# PSU.net
KiCad netlist of a schematic drawn in Altium Designer
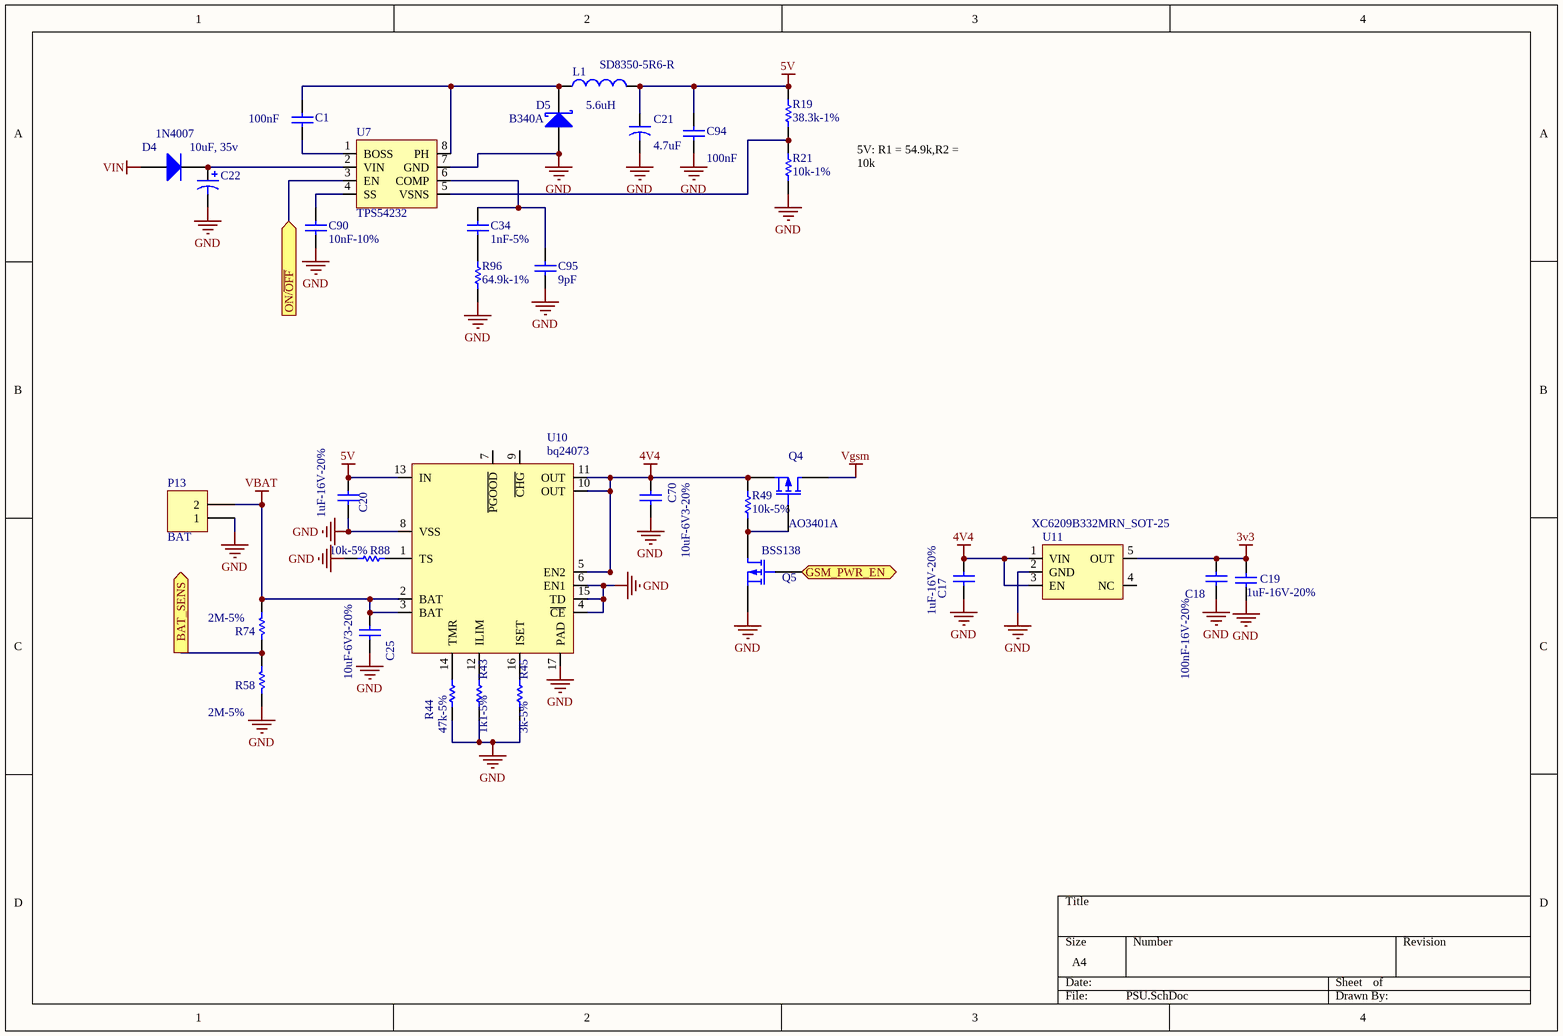
[diagram p0: PSU.SchDoc]

(export (version "E")
  (design (tool "Eeschema 10.0.6"))
  (components
    (comp (ref "C1")
      (value "100nF")
      (footprint "0402_TYPE1")
      (description "Capacitor")
      (fields (field (name "PUBLISHER") "Altium Limited"))
      (libsource (lib "Miscellaneous Devices") (part "Cap"))
    )
    (comp (ref "C17")
      (value "1uF-16V-20%")
      (footprint "C0603")
      (description "CAP CER 1UF 16V Y5V 0603")
      (fields
        (field (name "MANUFACTURER") "Yageo")
        (field (name "DIGI-KEY PART NUMBER") "311-1372-1-ND")
        (field (name "PUBLISHER") "Altium Limited")
      )
      (libsource (lib "Miscellaneous Devices") (part "Cap"))
    )
    (comp (ref "C18")
      (value "100nF-16V-20%")
      (footprint "0402_TYPE1")
      (description "CAP CER 0.1UF 16V Y5V 0402")
      (fields
        (field (name "MANUFACTURER") "Yageo")
        (field (name "DIGI-KEY PART NUMBER") "311-1047-1-ND")
        (field (name "PUBLISHER") "Altium Limited")
      )
      (libsource (lib "Miscellaneous Devices") (part "Cap"))
    )
    (comp (ref "C19")
      (value "1uF-16V-20%")
      (footprint "C0603")
      (description "CAP CER 1UF 16V Y5V 0603")
      (fields
        (field (name "MANUFACTURER") "Yageo")
        (field (name "DIGI-KEY PART NUMBER") "311-1372-1-ND")
        (field (name "PUBLISHER") "Altium Limited")
      )
      (libsource (lib "Miscellaneous Devices") (part "Cap"))
    )
    (comp (ref "C20")
      (value "1uF-16V-20%")
      (footprint "C0603")
      (description "CAP CER 1UF 16V Y5V 0603")
      (fields
        (field (name "MANUFACTURER") "Yageo")
        (field (name "DIGI-KEY PART NUMBER") "311-1372-1-ND")
        (field (name "PUBLISHER") "Altium Limited")
      )
      (libsource (lib "Miscellaneous Devices") (part "Cap"))
    )
    (comp (ref "C21")
      (value "4.7uF")
      (footprint "C1206")
      (description "Capacitor")
      (fields (field (name "PUBLISHER") "Altium Limited"))
      (libsource (lib "Miscellaneous Devices") (part "Cap2"))
    )
    (comp (ref "C22")
      (value "10uF, 35v")
      (footprint "CAPACITOR SIZE_C(D5.3)")
      (description "CAP ALUM 10UF 35V 20% SMD")
      (fields
        (field (name "DIGI-KEY PART NUMBER") "PCE3947TR-ND")
        (field (name "MANUFACTURER") "Panasonic Electronic Components")
        (field (name "PUBLISHER") "Altium Limited")
      )
      (libsource (lib "Miscellaneous Devices") (part "Cap Pol3"))
    )
    (comp (ref "C25")
      (value "10uF-6V3-20%")
      (footprint "C0603")
      (description "CAP CER 10UF 6.3V 20% X5R 0603")
      (fields
        (field (name "MANUFACTURER") "Yageo")
        (field (name "DIGI-KEY PART NUMBER") "311-1448-1-ND")
        (field (name "PUBLISHER") "Altium Limited")
      )
      (libsource (lib "Miscellaneous Devices") (part "Cap"))
    )
    (comp (ref "C34")
      (value "1nF-5%")
      (footprint "0402_TYPE1")
      (description "Non-Polarized Capacitor")
      (fields (field (name "DIGI-KEY PART NUMBER") "311-1122-1-ND") (field (name "MANUFACTURER") "Yageo"))
      (libsource (lib "Capacitor") (part "1nF-50V-C0805"))
    )
    (comp (ref "C70")
      (value "10uF-6V3-20%")
      (footprint "C0603")
      (description "CAP CER 10UF 6.3V 20% X5R 0603")
      (fields
        (field (name "MANUFACTURER") "Yageo")
        (field (name "DIGI-KEY PART NUMBER") "311-1448-1-ND")
        (field (name "PUBLISHER") "Altium Limited")
      )
      (libsource (lib "Miscellaneous Devices") (part "Cap"))
    )
    (comp (ref "C90")
      (value "10nF-10%")
      (footprint "0402_TYPE1")
      (description "Non-Polarized Capacitor")
      (fields (field (name "DIGI-KEY PART NUMBER") "311-1136-1-ND") (field (name "MANUFACTURER") "Yageo"))
      (libsource (lib "Capacitor") (part "10nF-50V-C0805"))
    )
    (comp (ref "C94")
      (value "100nF")
      (footprint "0402_TYPE1")
      (description "Capacitor")
      (fields (field (name "PUBLISHER") "Altium Limited"))
      (libsource (lib "Miscellaneous Devices") (part "Cap"))
    )
    (comp (ref "C95")
      (value "9pF")
      (footprint "0402_TYPE1")
      (description "Non-Polarized Capacitor")
      (fields (field (name "DIGI-KEY PART NUMBER") "311-1098-1-ND") (field (name "MANUFACTURER") "Yageo"))
      (libsource (lib "Capacitor") (part "9pF-50V-C0805"))
    )
    (comp (ref "D4")
      (value "1N4007")
      (footprint "DO-214AC (SMA)")
      (description "DIODE GEN PURPOSE 1000V 1A SMA")
      (fields
        (field (name "DIGI-KEY PART NUMBER") "641-1018-1-ND")
        (field (name "MANUFACTURER PART NUMBER") "CGRA4007-G")
        (field (name "PUBLISHER") "Altium Limited")
      )
      (libsource (lib "Miscellaneous Devices") (part "Diode"))
    )
    (comp (ref "D5")
      (value "B340A")
      (footprint "DO-214AC (SMA)")
      (description "DIODE SCHOTTKY 40V 3A SMA")
      (fields
        (field (name "DIGI-KEY PART NUMBER") "B340A-E3/61TGITR-ND")
        (field (name "MANUFACTURER PART NUMBER") "B340A-E3/61T")
        (field (name "PUBLISHER") "Altium Limited")
      )
      (libsource (lib "Miscellaneous Devices") (part "D Schottky"))
    )
    (comp (ref "L1")
      (value "SD8350-5R6-R")
      (footprint "SD8350-5R6-R")
      (description "Digikey part SD8350-4R7-R")
      (fields (field (name "ALTIUM_VALUE") "5.6uH") (field (name "PUBLISHER") "Altium Limited"))
      (libsource (lib "Miscellaneous Devices") (part "Inductor"))
    )
    (comp (ref "P13")
      (value "BAT")
      (footprint "HDR1X2")
      (description "Header, 2-Pin")
      (fields (field (name "PUBLISHER") "Altium Limited"))
      (libsource (lib "Miscellaneous Connectors") (part "Header 2"))
    )
    (comp (ref "Q4")
      (value "AO3401A")
      (footprint "SOT23-3")
      (description "MOSFET P-CH -30V -4.3A SOT23")
      (fields
        (field (name "DIGI-KEY PART NUMBER") "785-1001-1-ND")
        (field (name "MANUFACTURER") "Alpha & Omega Semiconductor Inc")
        (field (name "PUBLISHER") "Altium Limited")
      )
      (libsource (lib "Miscellaneous Devices") (part "MOSFET-P"))
    )
    (comp (ref "Q5")
      (value "BSS138")
      (footprint "SOT23-3")
      (description "MOSFET N-CH 50V 200MA SOT23-3")
      (fields
        (field (name "DIGI-KEY PART NUMBER") "BSS138-FDICT-ND")
        (field (name "MANUFACTURER") "Diodes Inc")
        (field (name "PUBLISHER") "Altium Limited")
      )
      (libsource (lib "") (part "MOSFET-P_1"))
    )
    (comp (ref "R19")
      (value "38.3k-1%")
      (footprint "R0402_TYPE1")
      (description "RES 38.3k OHM 1/4W 1% 0805 SMD")
      (fields (field (name "DIGI-KEY PART NUMBER") "311-38.3KCRTR-ND") (field (name "MANUFACTURER") "Yageo"))
      (libsource (lib "All_Resistor") (part "38.3k-1%-R0805"))
    )
    (comp (ref "R21")
      (value "10k-1%")
      (footprint "R0402_TYPE1")
      (description "RES 10k OHM 1/4W 1% 0805 SMD")
      (fields (field (name "DIGI-KEY PART NUMBER") "311-10.0KCRTR-ND") (field (name "MANUFACTURER") "Yageo"))
      (libsource (lib "All_Resistor") (part "10k-1%-R0805"))
    )
    (comp (ref "R43")
      (value "1k1-5%")
      (footprint "R0402_TYPE1")
      (description "RES 1.1K OHM 1/16W 5% 0402 SMD")
      (fields
        (field (name "DIGI-KEY PART NUMBER") "311-1.1KJRCT-ND")
        (field (name "MANUFACTURER") "Yageo")
        (field (name "PUBLISHER") "Altium Limited")
      )
      (libsource (lib "Miscellaneous Devices") (part "Res1"))
    )
    (comp (ref "R44")
      (value "47k-5%")
      (footprint "R0402_TYPE1")
      (description "RES 47K OHM 1/16W 5% 0402 SMD")
      (fields
        (field (name "DIGI-KEY PART NUMBER") "311-47KJRCT-ND")
        (field (name "MANUFACTURER") "Yageo")
        (field (name "PUBLISHER") "Altium Limited")
      )
      (libsource (lib "Miscellaneous Devices") (part "Res1"))
    )
    (comp (ref "R45")
      (value "3k-5%")
      (footprint "R0402_TYPE1")
      (description "RES 1.5K OHM 1/16W 5% 0402 SMD")
      (fields
        (field (name "DIGI-KEY PART NUMBER") "311-3.0KJRCT-ND")
        (field (name "MANUFACTURER") "Yageo")
        (field (name "PUBLISHER") "Altium Limited")
      )
      (libsource (lib "Miscellaneous Devices") (part "Res1"))
    )
    (comp (ref "R49")
      (value "10k-5%")
      (footprint "R0402_TYPE1")
      (description "RES 10K OHM 1/16W 5% 0402 SMD")
      (fields
        (field (name "DIGI-KEY PART NUMBER") "311-10KJRCT-ND")
        (field (name "MANUFACTURER") "Yageo")
        (field (name "PUBLISHER") "Altium Limited")
      )
      (libsource (lib "Miscellaneous Devices") (part "Res1"))
    )
    (comp (ref "R58")
      (value "2M-5%")
      (footprint "R0402_TYPE1")
      (description "RES 100K OHM 1/16W 5% 0402 SMD")
      (fields
        (field (name "DIGI-KEY PART NUMBER") "1276-4293-2-ND")
        (field (name "MANUFACTURER") "Samsung Electro-Mechanics America, Inc")
        (field (name "PUBLISHER") "Altium Limited")
      )
      (libsource (lib "Miscellaneous Devices") (part "Res1"))
    )
    (comp (ref "R74")
      (value "2M-5%")
      (footprint "R0402_TYPE1")
      (description "RES 2M OHM 1/16W 1% 0402")
      (fields
        (field (name "DIGI-KEY PART NUMBER") "1276-4293-2-ND")
        (field (name "MANUFACTURER") "Samsung Electro-Mechanics America, Inc")
        (field (name "PUBLISHER") "Altium Limited")
      )
      (libsource (lib "Miscellaneous Devices") (part "Res1"))
    )
    (comp (ref "R88")
      (value "10k-5%")
      (footprint "R0402_TYPE1")
      (description "RES 10K OHM 1/16W 5% 0402 SMD")
      (fields
        (field (name "DIGI-KEY PART NUMBER") "311-10KJRCT-ND")
        (field (name "MANUFACTURER") "Yageo")
        (field (name "PUBLISHER") "Altium Limited")
      )
      (libsource (lib "Miscellaneous Devices") (part "Res1"))
    )
    (comp (ref "R96")
      (value "64.9k-1%")
      (footprint "R0402_TYPE1")
      (description "RES 64.9k OHM 1/4W 1% 0805 SMD")
      (fields (field (name "DIGI-KEY PART NUMBER") "311-64.9KCRTR-ND") (field (name "MANUFACTURER") "Yageo"))
      (libsource (lib "All_Resistor") (part "64.9k-1%-R0805"))
    )
    (comp (ref "U7")
      (value "TPS54232")
      (footprint "SOIC127P600-8AL")
      (libsource (lib "TPS54232") (part "Component_1"))
    )
    (comp (ref "U10")
      (value "bq24073")
      (footprint "pq24073")
      (description "IC LI-ION CHARGE/PWR MGMT 16-QFN")
      (fields
        (field (name "DIGI-KEY PART NUMBER") "296-23839-1-ND")
        (field (name "MANUFACTURER") "Texas Instruments")
      )
      (libsource (lib "TI_Power") (part "BATTERY_CHARGER"))
    )
    (comp (ref "U11")
      (value "XC6209B332MRN_SOT-25")
      (footprint "SOT23-5")
      (fields (field (name "MANUFACTURER") "Tyrone"))
      (libsource (lib "Schlib1") (part "XC6209B332MRN_SOT-25"))
    )
  )
  (nets
    (net (code "1") (name "/BAT_SENS") (class "Default")
      (node (ref "R58") (pin "2") (pinfunction "2_2") (pintype "passive"))
      (node (ref "R74") (pin "1") (pinfunction "1_1") (pintype "passive"))
    )
    (net (code "2") (name "/GSM_PWR_EN") (class "Default")
      (node (ref "Q5") (pin "1") (pinfunction "G_1") (pintype "passive"))
    )
    (net (code "3") (name "/ON{slash}~{OFF}") (class "Default")
      (node (ref "U7") (pin "3") (pinfunction "EN_3") (pintype "passive"))
    )
    (net (code "4") (name "3v3") (class "Default")
      (node (ref "C18") (pin "2") (pinfunction "2_2") (pintype "passive"))
      (node (ref "C19") (pin "1") (pinfunction "1_1") (pintype "passive"))
      (node (ref "U11") (pin "5") (pinfunction "OUT_5") (pintype "passive"))
    )
    (net (code "5") (name "4V4") (class "Default")
      (node (ref "C17") (pin "1") (pinfunction "1_1") (pintype "passive"))
      (node (ref "C70") (pin "2") (pinfunction "2_2") (pintype "passive"))
      (node (ref "Q4") (pin "2") (pinfunction "S_2") (pintype "passive"))
      (node (ref "R49") (pin "1") (pinfunction "1_1") (pintype "passive"))
      (node (ref "U10") (pin "10") (pinfunction "OUT_10") (pintype "passive"))
      (node (ref "U10") (pin "11") (pinfunction "OUT_11") (pintype "passive"))
      (node (ref "U10") (pin "5") (pinfunction "EN2_5") (pintype "passive"))
      (node (ref "U11") (pin "1") (pinfunction "VIN_1") (pintype "passive"))
      (node (ref "U11") (pin "3") (pinfunction "EN_3") (pintype "passive"))
    )
    (net (code "6") (name "5V") (class "Default")
      (node (ref "C20") (pin "2") (pinfunction "2_2") (pintype "passive"))
      (node (ref "C21") (pin "1") (pinfunction "1_1") (pintype "passive"))
      (node (ref "C94") (pin "2") (pinfunction "2_2") (pintype "passive"))
      (node (ref "L1") (pin "2") (pinfunction "2_2") (pintype "passive"))
      (node (ref "R19") (pin "2") (pinfunction "2_2") (pintype "passive"))
      (node (ref "U10") (pin "13") (pinfunction "IN_13") (pintype "passive"))
    )
    (net (code "7") (name "GND") (class "Default")
      (node (ref "C17") (pin "2") (pinfunction "2_2") (pintype "passive"))
      (node (ref "C18") (pin "1") (pinfunction "1_1") (pintype "passive"))
      (node (ref "C19") (pin "2") (pinfunction "2_2") (pintype "passive"))
      (node (ref "C20") (pin "1") (pinfunction "1_1") (pintype "passive"))
      (node (ref "C21") (pin "2") (pinfunction "2_2") (pintype "passive"))
      (node (ref "C22") (pin "2") (pinfunction "2_2") (pintype "passive"))
      (node (ref "C25") (pin "1") (pinfunction "1_1") (pintype "passive"))
      (node (ref "C70") (pin "1") (pinfunction "1_1") (pintype "passive"))
      (node (ref "C90") (pin "1") (pinfunction "1_1") (pintype "passive"))
      (node (ref "C94") (pin "1") (pinfunction "1_1") (pintype "passive"))
      (node (ref "C95") (pin "1") (pinfunction "1_1") (pintype "passive"))
      (node (ref "D5") (pin "1") (pinfunction "A_1") (pintype "passive"))
      (node (ref "P13") (pin "1") (pinfunction "1_1") (pintype "passive"))
      (node (ref "Q5") (pin "2") (pinfunction "S_2") (pintype "passive"))
      (node (ref "R21") (pin "1") (pinfunction "1_1") (pintype "passive"))
      (node (ref "R43") (pin "2") (pinfunction "2_2") (pintype "passive"))
      (node (ref "R44") (pin "2") (pinfunction "2_2") (pintype "passive"))
      (node (ref "R45") (pin "2") (pinfunction "2_2") (pintype "passive"))
      (node (ref "R58") (pin "1") (pinfunction "1_1") (pintype "passive"))
      (node (ref "R88") (pin "2") (pinfunction "2_2") (pintype "passive"))
      (node (ref "R96") (pin "1") (pinfunction "1_1") (pintype "passive"))
      (node (ref "U10") (pin "15") (pinfunction "TD_15") (pintype "passive"))
      (node (ref "U10") (pin "17") (pinfunction "PAD_17") (pintype "passive"))
      (node (ref "U10") (pin "4") (pinfunction "~{CE}_4") (pintype "passive"))
      (node (ref "U10") (pin "6") (pinfunction "EN1_6") (pintype "passive"))
      (node (ref "U10") (pin "8") (pinfunction "VSS_8") (pintype "passive"))
      (node (ref "U11") (pin "2") (pinfunction "GND_2") (pintype "passive"))
      (node (ref "U7") (pin "7") (pinfunction "GND_7") (pintype "passive"))
    )
    (net (code "8") (name "Net-(C34-Pad1)") (class "Default")
      (node (ref "C34") (pin "1") (pinfunction "1_1") (pintype "passive"))
      (node (ref "R96") (pin "2") (pinfunction "2_2") (pintype "passive"))
    )
    (net (code "9") (name "Net-(D4-K)") (class "Default")
      (node (ref "C22") (pin "1") (pinfunction "1_1") (pintype "passive"))
      (node (ref "D4") (pin "2") (pinfunction "K_2") (pintype "passive"))
      (node (ref "U7") (pin "2") (pinfunction "VIN_2") (pintype "passive"))
    )
    (net (code "10") (name "Net-(D5-K)") (class "Default")
      (node (ref "C1") (pin "1") (pinfunction "1_1") (pintype "passive"))
      (node (ref "D5") (pin "2") (pinfunction "K_2") (pintype "passive"))
      (node (ref "L1") (pin "1") (pinfunction "1_1") (pintype "passive"))
      (node (ref "U7") (pin "8") (pinfunction "PH_8") (pintype "passive"))
    )
    (net (code "11") (name "Net-(Q4-G)") (class "Default")
      (node (ref "Q4") (pin "1") (pinfunction "G_1") (pintype "passive"))
      (node (ref "Q5") (pin "3") (pinfunction "D_3") (pintype "passive"))
      (node (ref "R49") (pin "2") (pinfunction "2_2") (pintype "passive"))
    )
    (net (code "12") (name "Net-(U7-BOSS)") (class "Default")
      (node (ref "C1") (pin "2") (pinfunction "2_2") (pintype "passive"))
      (node (ref "U7") (pin "1") (pinfunction "BOSS_1") (pintype "passive"))
    )
    (net (code "13") (name "Net-(U7-COMP)") (class "Default")
      (node (ref "C34") (pin "2") (pinfunction "2_2") (pintype "passive"))
      (node (ref "C95") (pin "2") (pinfunction "2_2") (pintype "passive"))
      (node (ref "U7") (pin "6") (pinfunction "COMP_6") (pintype "passive"))
    )
    (net (code "14") (name "Net-(U7-SS)") (class "Default")
      (node (ref "C90") (pin "2") (pinfunction "2_2") (pintype "passive"))
      (node (ref "U7") (pin "4") (pinfunction "SS_4") (pintype "passive"))
    )
    (net (code "15") (name "Net-(U7-VSNS)") (class "Default")
      (node (ref "R19") (pin "1") (pinfunction "1_1") (pintype "passive"))
      (node (ref "R21") (pin "2") (pinfunction "2_2") (pintype "passive"))
      (node (ref "U7") (pin "5") (pinfunction "VSNS_5") (pintype "passive"))
    )
    (net (code "16") (name "Net-(U10-ILIM)") (class "Default")
      (node (ref "R43") (pin "1") (pinfunction "1_1") (pintype "passive"))
      (node (ref "U10") (pin "12") (pinfunction "ILIM_12") (pintype "passive"))
    )
    (net (code "17") (name "Net-(U10-ISET)") (class "Default")
      (node (ref "R45") (pin "1") (pinfunction "1_1") (pintype "passive"))
      (node (ref "U10") (pin "16") (pinfunction "ISET_16") (pintype "passive"))
    )
    (net (code "18") (name "Net-(U10-TMR)") (class "Default")
      (node (ref "R44") (pin "1") (pinfunction "1_1") (pintype "passive"))
      (node (ref "U10") (pin "14") (pinfunction "TMR_14") (pintype "passive"))
    )
    (net (code "19") (name "Net-(U10-TS)") (class "Default")
      (node (ref "R88") (pin "1") (pinfunction "1_1") (pintype "passive"))
      (node (ref "U10") (pin "1") (pinfunction "TS_1") (pintype "passive"))
    )
    (net (code "20") (name "VBAT") (class "Default")
      (node (ref "C25") (pin "2") (pinfunction "2_2") (pintype "passive"))
      (node (ref "P13") (pin "2") (pinfunction "2_2") (pintype "passive"))
      (node (ref "R74") (pin "2") (pinfunction "2_2") (pintype "passive"))
      (node (ref "U10") (pin "2") (pinfunction "BAT_2") (pintype "passive"))
      (node (ref "U10") (pin "3") (pinfunction "BAT_3") (pintype "passive"))
    )
    (net (code "21") (name "VIN") (class "Default")
      (node (ref "D4") (pin "1") (pinfunction "A_1") (pintype "passive"))
    )
    (net (code "22") (name "Vgsm") (class "Default")
      (node (ref "Q4") (pin "3") (pinfunction "D_3") (pintype "passive"))
    )
    (net (code "23") (name "unconnected-(U10-~{CHG}-Pad9)") (class "Default")
      (node (ref "U10") (pin "9") (pinfunction "~{CHG}_9") (pintype "passive"))
    )
    (net (code "24") (name "unconnected-(U10-~{PGOOD}-Pad7)") (class "Default")
      (node (ref "U10") (pin "7") (pinfunction "~{PGOOD}_7") (pintype "passive"))
    )
    (net (code "25") (name "unconnected-(U11-NC-Pad4)") (class "Default")
      (node (ref "U11") (pin "4") (pinfunction "NC_4") (pintype "passive"))
    )
  )
)
